# LIDO-HW_300_VehicleInterface.net
KiCad netlist of a schematic drawn in Altium Designer
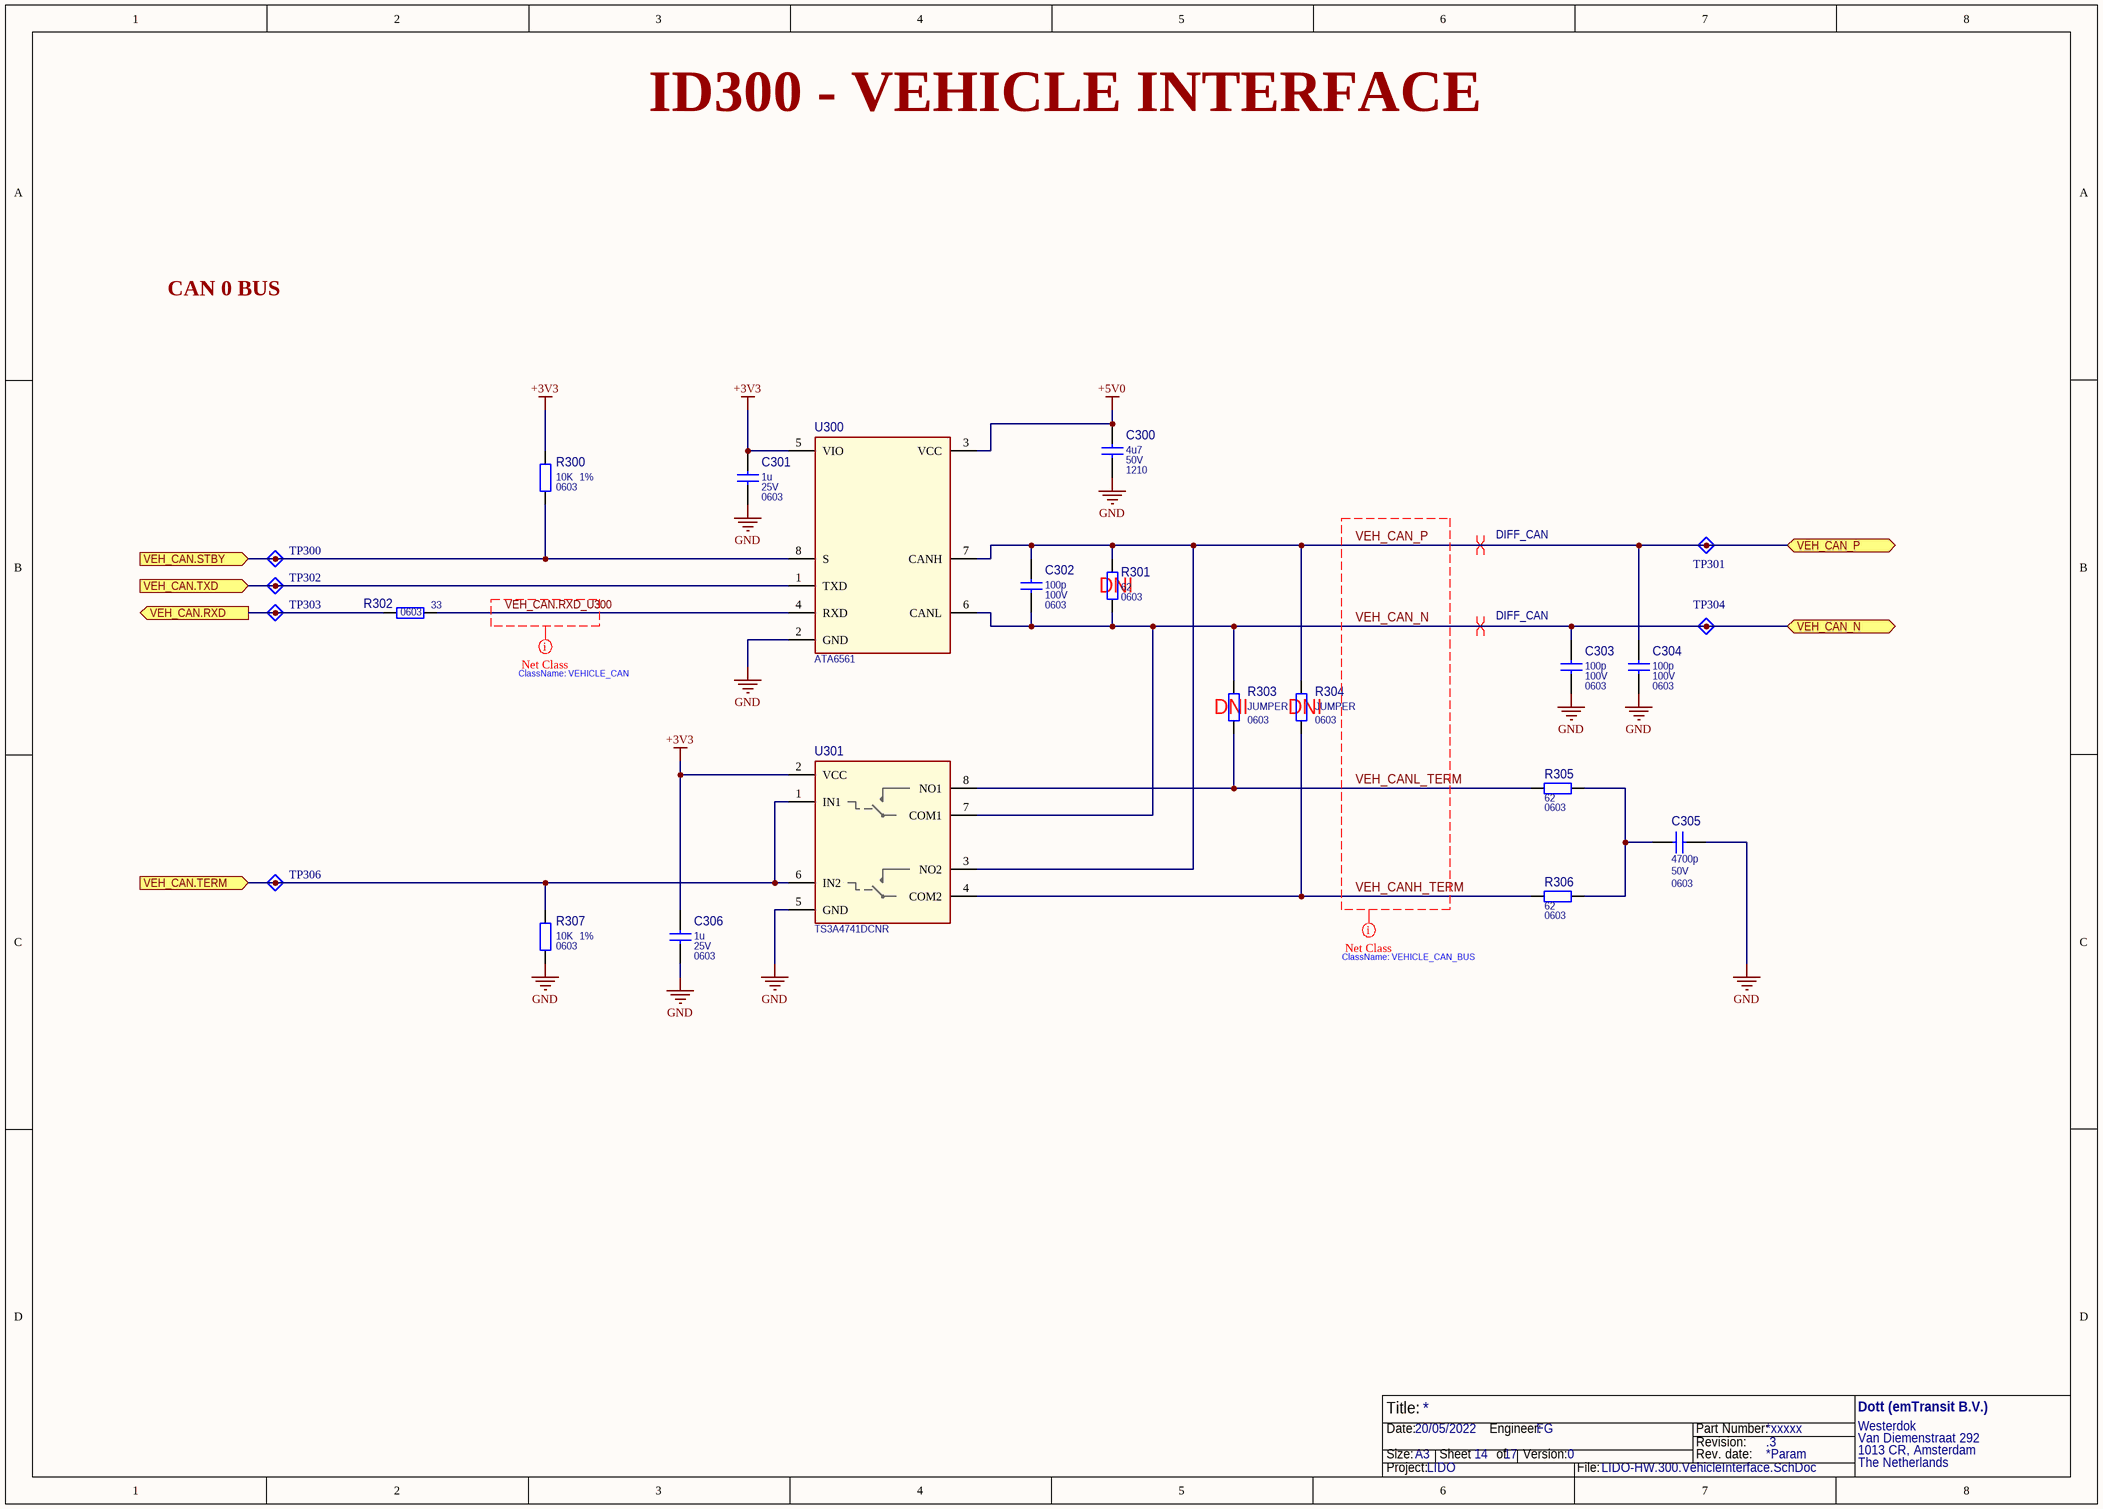
[diagram p0: LIDO-HW.300.VehicleInterface.SchDoc]

(export (version "E")
  (design (tool "Eeschema 10.0.6"))
  (components
    (comp (ref "C300")
      (value "4u7")
      (footprint "CAP_1210_3225X180-N_MURATA_A")
      (description "CAP CER 4.7UF 50V X7R 1210")
      (fields
        (field (name "MANUFACTURER PART NUMBER") "CL32B475KBJVPNE")
        (field (name "MANUFACTURER") "Samsung Electro-Mechanics")
        (field (name "PART VALUE 2") "50V")
        (field (name "PART PACKAGE") "1210")
      )
      (libsource (lib "DB_Library") (part "Ceramic"))
    )
    (comp (ref "C301")
      (value "1u")
      (footprint "CAP_0603_1608X90-N_MURATA_A")
      (description "CAP CER 1UF 25V X7R 0603")
      (fields
        (field (name "MANUFACTURER PART NUMBER") "CGA3E1X7R1E105M080AE")
        (field (name "MANUFACTURER") "TDK Corporation")
        (field (name "PART VALUE 2") "25V")
        (field (name "PART PACKAGE") "0603")
      )
      (libsource (lib "DB_Library") (part "Ceramic"))
    )
    (comp (ref "C302")
      (value "100p")
      (footprint "CAP_0603_1608X90-N_MURATA_A")
      (description "CAP CER 100PF 100V C0G 0603")
      (fields
        (field (name "MANUFACTURER PART NUMBER") "CGA3E2C0G2A101J080AA")
        (field (name "MANUFACTURER") "TDK Corporation")
        (field (name "PART VALUE 2") "100V")
        (field (name "PART PACKAGE") "0603")
      )
      (libsource (lib "DB_Library") (part "Ceramic"))
    )
    (comp (ref "C303")
      (value "100p")
      (footprint "CAP_0603_1608X90-N_MURATA_A")
      (description "CAP CER 100PF 100V C0G 0603")
      (fields
        (field (name "MANUFACTURER PART NUMBER") "CGA3E2C0G2A101J080AA")
        (field (name "MANUFACTURER") "TDK Corporation")
        (field (name "PART VALUE 2") "100V")
        (field (name "PART PACKAGE") "0603")
      )
      (libsource (lib "DB_Library") (part "Ceramic"))
    )
    (comp (ref "C304")
      (value "100p")
      (footprint "CAP_0603_1608X90-N_MURATA_A")
      (description "CAP CER 100PF 100V C0G 0603")
      (fields
        (field (name "MANUFACTURER PART NUMBER") "CGA3E2C0G2A101J080AA")
        (field (name "MANUFACTURER") "TDK Corporation")
        (field (name "PART VALUE 2") "100V")
        (field (name "PART PACKAGE") "0603")
      )
      (libsource (lib "DB_Library") (part "Ceramic"))
    )
    (comp (ref "C305")
      (value "4700p")
      (footprint "CAP_0603_1608X90-N_MURATA_A")
      (description "CAP CER 4700PF 50V X7R 0603")
      (fields
        (field (name "MANUFACTURER PART NUMBER") "CGA3E2X7R1H472K080AA")
        (field (name "MANUFACTURER") "TDK Corporation")
        (field (name "PART VALUE 2") "50V")
        (field (name "PART PACKAGE") "0603")
      )
      (libsource (lib "DB_Library") (part "Ceramic"))
    )
    (comp (ref "C306")
      (value "1u")
      (footprint "CAP_0603_1608X90-N_MURATA_A")
      (description "CAP CER 1UF 25V X7R 0603")
      (fields
        (field (name "MANUFACTURER PART NUMBER") "CGA3E1X7R1E105M080AE")
        (field (name "MANUFACTURER") "TDK Corporation")
        (field (name "PART VALUE 2") "25V")
        (field (name "PART PACKAGE") "0603")
      )
      (libsource (lib "DB_Library") (part "Ceramic"))
    )
    (comp (ref "R300")
      (value "10K")
      (footprint "RES_0603_1608X60-N_YAGEO_A")
      (description "RES 10K OHM 1% 1/10W 0603")
      (fields
        (field (name "MANUFACTURER PART NUMBER") "RC0603FR-0710KL")
        (field (name "MANUFACTURER") "YAGEO")
        (field (name "PART VALUE 2") "1%")
        (field (name "PART PACKAGE") "0603")
      )
      (libsource (lib "DB_Library") (part "Resistor"))
    )
    (comp (ref "R301")
      (value "62")
      (footprint "RES_0603_1608X60-N_YAGEO_A")
      (description "RES SMD 62 OHM 1% 1/10W 0603")
      (fields
        (field (name "MANUFACTURER PART NUMBER") "ERJ-3EKF62R0V")
        (field (name "MANUFACTURER") "Panasonic Electronic Components")
        (field (name "PART PACKAGE") "0603")
      )
      (libsource (lib "DB_Library") (part "Resistor"))
    )
    (comp (ref "R302")
      (value "33")
      (footprint "RES_0603_1608X60-N_YAGEO_A")
      (description "RES 33 OHM 5% 1/10W 0603")
      (fields
        (field (name "MANUFACTURER PART NUMBER") "RC0603JR-0733RL")
        (field (name "MANUFACTURER") "YAGEO")
        (field (name "PART PACKAGE") "0603")
      )
      (libsource (lib "") (part "Resistor_1"))
    )
    (comp (ref "R303")
      (value "JUMPER")
      (footprint "RES_0603_1608X60-N_YAGEO_A")
      (description "RES 0 OHM JUMPER 1/10W 0603")
      (fields
        (field (name "MANUFACTURER PART NUMBER") "RC0603JR-070RL")
        (field (name "MANUFACTURER") "YAGEO")
        (field (name "PART PACKAGE") "0603")
      )
      (libsource (lib "DB_Library") (part "Resistor"))
    )
    (comp (ref "R304")
      (value "JUMPER")
      (footprint "RES_0603_1608X60-N_YAGEO_A")
      (description "RES 0 OHM JUMPER 1/10W 0603")
      (fields
        (field (name "MANUFACTURER PART NUMBER") "RC0603JR-070RL")
        (field (name "MANUFACTURER") "YAGEO")
        (field (name "PART PACKAGE") "0603")
      )
      (libsource (lib "DB_Library") (part "Resistor"))
    )
    (comp (ref "R305")
      (value "62")
      (footprint "RES_0603_1608X60-N_YAGEO_A")
      (description "RES SMD 62 OHM 1% 1/10W 0603")
      (fields
        (field (name "MANUFACTURER PART NUMBER") "ERJ-3EKF62R0V")
        (field (name "MANUFACTURER") "Panasonic Electronic Components")
        (field (name "PART PACKAGE") "0603")
      )
      (libsource (lib "") (part "Resistor_1"))
    )
    (comp (ref "R306")
      (value "62")
      (footprint "RES_0603_1608X60-N_YAGEO_A")
      (description "RES SMD 62 OHM 1% 1/10W 0603")
      (fields
        (field (name "MANUFACTURER PART NUMBER") "ERJ-3EKF62R0V")
        (field (name "MANUFACTURER") "Panasonic Electronic Components")
        (field (name "PART PACKAGE") "0603")
      )
      (libsource (lib "") (part "Resistor_1"))
    )
    (comp (ref "R307")
      (value "10K")
      (footprint "RES_0603_1608X60-N_YAGEO_A")
      (description "RES 10K OHM 1% 1/10W 0603")
      (fields
        (field (name "MANUFACTURER PART NUMBER") "RC0603FR-0710KL")
        (field (name "MANUFACTURER") "YAGEO")
        (field (name "PART VALUE 2") "1%")
        (field (name "PART PACKAGE") "0603")
      )
      (libsource (lib "DB_Library") (part "Resistor"))
    )
    (comp (ref "TP300")
      (value "TestPoint_A")
      (footprint "TESTPOINT_1D_A")
      (description "Pad Diamater 1mm")
      (fields (field (name "PART") "Test Point 1D A") (field (name "OBSOLETE PART") "False"))
      (libsource (lib "DB_Library") (part "TestPoint_A"))
    )
    (comp (ref "TP301")
      (value "TestPoint_A")
      (footprint "TESTPOINT_1D_A")
      (description "Pad Diamater 1mm")
      (fields (field (name "PART") "Test Point 1D A") (field (name "OBSOLETE PART") "False"))
      (libsource (lib "DB_Library") (part "TestPoint_A"))
    )
    (comp (ref "TP302")
      (value "TestPoint_A")
      (footprint "TESTPOINT_1D_A")
      (description "Pad Diamater 1mm")
      (fields (field (name "PART") "Test Point 1D A") (field (name "OBSOLETE PART") "False"))
      (libsource (lib "DB_Library") (part "TestPoint_A"))
    )
    (comp (ref "TP303")
      (value "TestPoint_A")
      (footprint "TESTPOINT_1D_A")
      (description "Pad Diamater 1mm")
      (fields (field (name "PART") "Test Point 1D A") (field (name "OBSOLETE PART") "False"))
      (libsource (lib "DB_Library") (part "TestPoint_A"))
    )
    (comp (ref "TP304")
      (value "TestPoint_A")
      (footprint "TESTPOINT_1D_A")
      (description "Pad Diamater 1mm")
      (fields (field (name "PART") "Test Point 1D A") (field (name "OBSOLETE PART") "False"))
      (libsource (lib "DB_Library") (part "TestPoint_A"))
    )
    (comp (ref "TP306")
      (value "TestPoint_A")
      (footprint "TESTPOINT_1D_A")
      (description "Pad Diamater 1mm")
      (fields (field (name "PART") "Test Point 1D A") (field (name "OBSOLETE PART") "False"))
      (libsource (lib "DB_Library") (part "TestPoint_A"))
    )
    (comp (ref "U300")
      (value "ATA6561")
      (footprint "SOIC8P127_490X600X175L84X41-N_TI_A")
      (description "IC TRANSCEIVER 1/1 8SO")
      (fields
        (field (name "MANUFACTURER") "Microchip Technology")
        (field (name "MANUFACTURER PART NUMBER") "ATA6561-GAQW")
        (field (name "DESIGNER") "Matt Drazenovich")
        (field (name "REVIEWED") "Dekimo_07-07-2020")
      )
      (libsource (lib "DB_Library") (part "ATA6561_A"))
    )
    (comp (ref "U301")
      (value "TS3A4741DCNR")
      (footprint "SOT23-8P65_280X145L45-N_TI_A")
      (description "IC SWITCH DUAL SPST SOT23-8")
      (fields
        (field (name "MANUFACTURER") "Texas Instruments")
        (field (name "OBSOLETE PART") "False")
        (field (name "DESIGNER") "Matt Drazenovich")
        (field (name "REVIEWED") "Not Footprint")
      )
      (libsource (lib "DB_Library") (part "TS3A4741D_A"))
    )
  )
  (nets
    (net (code "1") (name "+3V3") (class "Default")
      (node (ref "C301") (pin "1") (pinfunction "1_1") (pintype "passive"))
      (node (ref "C306") (pin "1") (pinfunction "1_1") (pintype "passive"))
      (node (ref "R300") (pin "2") (pinfunction "2_2") (pintype "passive"))
      (node (ref "U300") (pin "5") (pinfunction "VIO_5") (pintype "power_in"))
      (node (ref "U301") (pin "2") (pinfunction "VCC_2") (pintype "power_in"))
    )
    (net (code "2") (name "+5V0") (class "Default")
      (node (ref "C300") (pin "1") (pinfunction "1_1") (pintype "passive"))
      (node (ref "U300") (pin "3") (pinfunction "VCC_3") (pintype "power_in"))
    )
    (net (code "3") (name "/VEH_CAN.RXD") (class "Default")
      (node (ref "R302") (pin "1") (pinfunction "1_1") (pintype "passive"))
      (node (ref "TP303") (pin "1") (pinfunction "TP_1") (pintype "passive"))
    )
    (net (code "4") (name "/VEH_CAN.RXD_U300") (class "Default")
      (node (ref "R302") (pin "2") (pinfunction "2_2") (pintype "passive"))
      (node (ref "U300") (pin "4") (pinfunction "RXD_4") (pintype "passive"))
    )
    (net (code "5") (name "/VEH_CAN.STBY") (class "Default")
      (node (ref "R300") (pin "1") (pinfunction "1_1") (pintype "passive"))
      (node (ref "TP300") (pin "1") (pinfunction "TP_1") (pintype "passive"))
      (node (ref "U300") (pin "8") (pinfunction "S_8") (pintype "passive"))
    )
    (net (code "6") (name "/VEH_CAN.TERM") (class "Default")
      (node (ref "R307") (pin "2") (pinfunction "2_2") (pintype "passive"))
      (node (ref "TP306") (pin "1") (pinfunction "TP_1") (pintype "passive"))
      (node (ref "U301") (pin "1") (pinfunction "IN1_1") (pintype "passive"))
      (node (ref "U301") (pin "6") (pinfunction "IN2_6") (pintype "passive"))
    )
    (net (code "7") (name "/VEH_CAN.TXD") (class "Default")
      (node (ref "TP302") (pin "1") (pinfunction "TP_1") (pintype "passive"))
      (node (ref "U300") (pin "1") (pinfunction "TXD_1") (pintype "passive"))
    )
    (net (code "8") (name "/VEH_CANH_TERM") (class "Default")
      (node (ref "R304") (pin "1") (pinfunction "1_1") (pintype "passive"))
      (node (ref "R306") (pin "1") (pinfunction "1_1") (pintype "passive"))
      (node (ref "U301") (pin "4") (pinfunction "COM2_4") (pintype "passive"))
    )
    (net (code "9") (name "/VEH_CANL_TERM") (class "Default")
      (node (ref "R303") (pin "1") (pinfunction "1_1") (pintype "passive"))
      (node (ref "R305") (pin "1") (pinfunction "1_1") (pintype "passive"))
      (node (ref "U301") (pin "8") (pinfunction "NO1_8") (pintype "passive"))
    )
    (net (code "10") (name "/VEH_CAN_N") (class "Default")
      (node (ref "C302") (pin "2") (pinfunction "2_2") (pintype "passive"))
      (node (ref "C303") (pin "1") (pinfunction "1_1") (pintype "passive"))
      (node (ref "R301") (pin "1") (pinfunction "1_1") (pintype "passive"))
      (node (ref "R303") (pin "2") (pinfunction "2_2") (pintype "passive"))
      (node (ref "TP304") (pin "1") (pinfunction "TP_1") (pintype "passive"))
      (node (ref "U300") (pin "6") (pinfunction "CANL_6") (pintype "passive"))
      (node (ref "U301") (pin "7") (pinfunction "COM1_7") (pintype "passive"))
    )
    (net (code "11") (name "/VEH_CAN_P") (class "Default")
      (node (ref "C302") (pin "1") (pinfunction "1_1") (pintype "passive"))
      (node (ref "C304") (pin "1") (pinfunction "1_1") (pintype "passive"))
      (node (ref "R301") (pin "2") (pinfunction "2_2") (pintype "passive"))
      (node (ref "R304") (pin "2") (pinfunction "2_2") (pintype "passive"))
      (node (ref "TP301") (pin "1") (pinfunction "TP_1") (pintype "passive"))
      (node (ref "U300") (pin "7") (pinfunction "CANH_7") (pintype "passive"))
      (node (ref "U301") (pin "3") (pinfunction "NO2_3") (pintype "passive"))
    )
    (net (code "12") (name "GND") (class "Default")
      (node (ref "C300") (pin "2") (pinfunction "2_2") (pintype "passive"))
      (node (ref "C301") (pin "2") (pinfunction "2_2") (pintype "passive"))
      (node (ref "C303") (pin "2") (pinfunction "2_2") (pintype "passive"))
      (node (ref "C304") (pin "2") (pinfunction "2_2") (pintype "passive"))
      (node (ref "C305") (pin "2") (pinfunction "2_2") (pintype "passive"))
      (node (ref "C306") (pin "2") (pinfunction "2_2") (pintype "passive"))
      (node (ref "R307") (pin "1") (pinfunction "1_1") (pintype "passive"))
      (node (ref "U300") (pin "2") (pinfunction "GND_2") (pintype "power_in"))
      (node (ref "U301") (pin "5") (pinfunction "GND_5") (pintype "power_in"))
    )
    (net (code "13") (name "Net-(C305-Pad1)") (class "Default")
      (node (ref "C305") (pin "1") (pinfunction "1_1") (pintype "passive"))
      (node (ref "R305") (pin "2") (pinfunction "2_2") (pintype "passive"))
      (node (ref "R306") (pin "2") (pinfunction "2_2") (pintype "passive"))
    )
  )
)
